# Sensors.net
KiCad netlist of a schematic drawn in Altium Designer
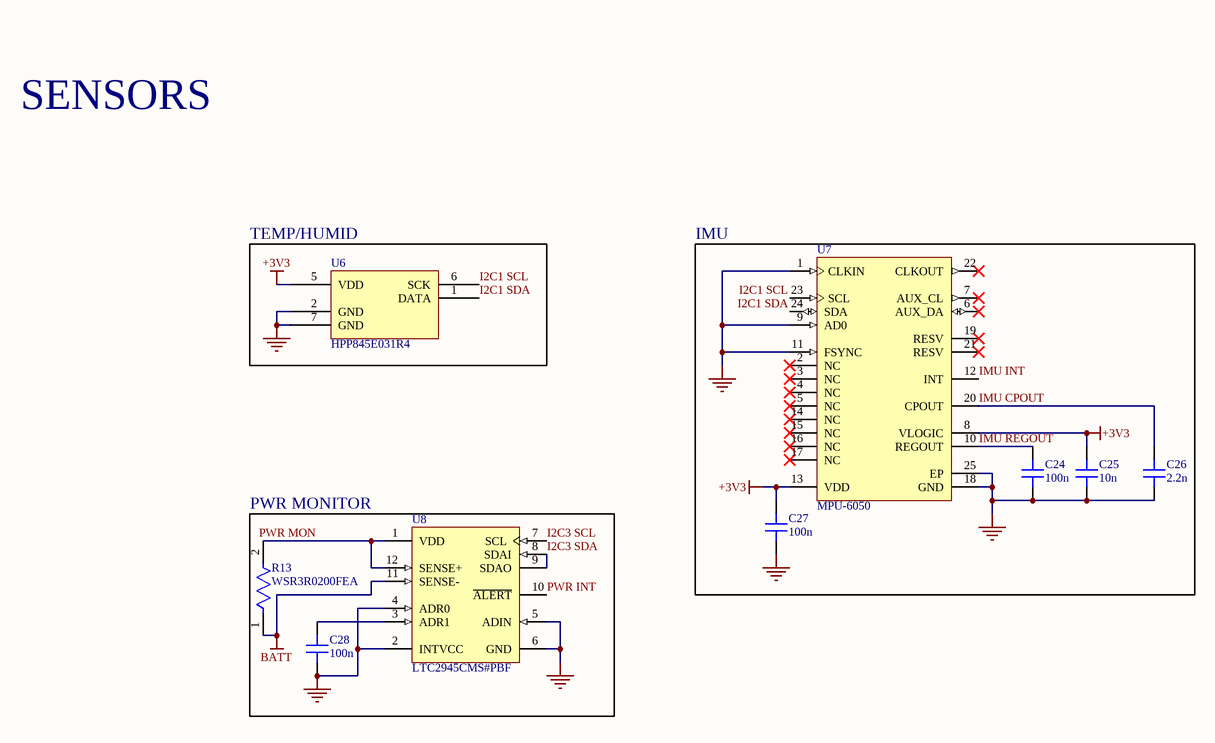
[diagram p0: Sensors.SchDoc]

(export (version "E")
  (design (tool "Eeschema 10.0.6"))
  (components
    (comp (ref "C24")
      (value "100n")
      (footprint "CAP 0402_1005")
      (description "CAP CER 100NF 10V X7R 0402")
      (fields (field (name "PART NUMBER") "CL05B104KP5VPNC"))
      (libsource (lib "Celestial Altium Library - altium_library") (part "Capacitor"))
    )
    (comp (ref "C25")
      (value "10n")
      (footprint "CAP 0402_1005")
      (description "CAP CER 0402 10NF 50V X7R 5%")
      (fields (field (name "PART NUMBER") "C0402C103J5RECAUTO"))
      (libsource (lib "Celestial Altium Library - altium_library") (part "Capacitor"))
    )
    (comp (ref "C26")
      (value "2.2n")
      (footprint "CAP 0402_1005")
      (description "CAP CER 0402 2.2NF 25V C0G 5%")
      (fields (field (name "PART NUMBER") "C0402C222J3GEC7867"))
      (libsource (lib "Celestial Altium Library - altium_library") (part "Capacitor"))
    )
    (comp (ref "C27")
      (value "100n")
      (footprint "CAP 0402_1005")
      (description "CAP CER 100NF 10V X7R 0402")
      (fields (field (name "PART NUMBER") "CL05B104KP5VPNC"))
      (libsource (lib "Celestial Altium Library - altium_library") (part "Capacitor"))
    )
    (comp (ref "C28")
      (value "100n")
      (footprint "CAP 0402_1005")
      (description "CAP CER 100NF 10V X7R 0402")
      (fields (field (name "PART NUMBER") "CL05B104KP5VPNC"))
      (libsource (lib "Celestial Altium Library - altium_library") (part "Capacitor"))
    )
    (comp (ref "R13")
      (value "WSR3R0200FEA")
      (footprint "FP-WSR3-MFG")
      (description "WSR3R0200FEA Res Metal Strip 4527 0.02 Ohm 1% 3W ±75ppm/°C Molded SMD SMD Embossed Plastic T/R")
      (fields (field (name "TOLERANCE") "1%"))
      (libsource (lib "Altium Content Vault") (part "1029c3af85768c4190bb7ad29bc67b5"))
    )
    (comp (ref "U6")
      (value "HPP845E031R4")
      (footprint "TE HPP845E031R4")
      (description "SENSOR HUMID/TEMP 3V I2C 2% SMD")
      (libsource (lib "Celestial Altium Library - altium_library") (part "TE HPP845E031R4"))
    )
    (comp (ref "U7")
      (value "MPU-6050")
      (footprint "IS-QFN-24_V")
      (fields (field (name "MANUFACTURER") "InvenSense"))
      (libsource (lib "Altium Content Vault") (part "IS-MPU-6050-QFN-24"))
    )
    (comp (ref "U8")
      (value "LTC2945CMS#PBF")
      (footprint "LT-MS-12_M")
      (description "Wide Range I2C Power Monitor, 12-pin SOP (MS-12), 0 to 70 degC, Pb-Free")
      (fields (field (name "MANUFACTURER") "Linear Technology"))
      (libsource (lib "Altium Content Vault") (part "LT-LTC2945-MS-12"))
    )
  )
  (nets
    (net (code "1") (name "+3V3") (class "Default")
      (node (ref "C25") (pin "2") (pinfunction "2_2") (pintype "passive"))
      (node (ref "C27") (pin "2") (pinfunction "2_2") (pintype "passive"))
      (node (ref "U6") (pin "5") (pinfunction "VDD_5") (pintype "passive"))
      (node (ref "U7") (pin "13") (pinfunction "VDD_13") (pintype "power_in"))
      (node (ref "U7") (pin "8") (pinfunction "VLOGIC_8") (pintype "power_in"))
    )
    (net (code "2") (name "/I2C1 SCL") (class "Default")
      (node (ref "U6") (pin "6") (pinfunction "SCK_6") (pintype "passive"))
      (node (ref "U7") (pin "23") (pinfunction "SCL_23") (pintype "input"))
    )
    (net (code "3") (name "/I2C1 SDA") (class "Default")
      (node (ref "U6") (pin "1") (pinfunction "DATA_1") (pintype "passive"))
      (node (ref "U7") (pin "24") (pinfunction "SDA_24") (pintype "bidirectional"))
    )
    (net (code "4") (name "/I2C3 SCL") (class "Default")
      (node (ref "U8") (pin "7") (pinfunction "SCL_7") (pintype "input"))
    )
    (net (code "5") (name "/I2C3 SDA") (class "Default")
      (node (ref "U8") (pin "8") (pinfunction "SDAI_8") (pintype "input"))
      (node (ref "U8") (pin "9") (pinfunction "SDAO_9") (pintype "open_collector"))
    )
    (net (code "6") (name "/IMU CPOUT") (class "Default")
      (node (ref "C26") (pin "2") (pinfunction "2_2") (pintype "passive"))
      (node (ref "U7") (pin "20") (pinfunction "CPOUT_20") (pintype "passive"))
    )
    (net (code "7") (name "/IMU INT") (class "Default")
      (node (ref "U7") (pin "12") (pinfunction "INT_12") (pintype "open_collector"))
    )
    (net (code "8") (name "/IMU REGOUT") (class "Default")
      (node (ref "C24") (pin "2") (pinfunction "2_2") (pintype "passive"))
      (node (ref "U7") (pin "10") (pinfunction "REGOUT_10") (pintype "passive"))
    )
    (net (code "9") (name "/PWR INT") (class "Default")
      (node (ref "U8") (pin "10") (pinfunction "~{ALERT}_10") (pintype "open_collector"))
    )
    (net (code "10") (name "/PWR MON") (class "Default")
      (node (ref "R13") (pin "2") (pinfunction "2_2") (pintype "passive"))
      (node (ref "U8") (pin "1") (pinfunction "VDD_1") (pintype "power_in"))
      (node (ref "U8") (pin "12") (pinfunction "SENSE+_12") (pintype "input"))
    )
    (net (code "11") (name "BATT") (class "Default")
      (node (ref "R13") (pin "1") (pinfunction "1_1") (pintype "passive"))
      (node (ref "U8") (pin "11") (pinfunction "SENSE-_11") (pintype "input"))
    )
    (net (code "12") (name "GND") (class "Default")
      (node (ref "C24") (pin "1") (pinfunction "1_1") (pintype "passive"))
      (node (ref "C25") (pin "1") (pinfunction "1_1") (pintype "passive"))
      (node (ref "C26") (pin "1") (pinfunction "1_1") (pintype "passive"))
      (node (ref "C27") (pin "1") (pinfunction "1_1") (pintype "passive"))
      (node (ref "C28") (pin "1") (pinfunction "1_1") (pintype "passive"))
      (node (ref "U6") (pin "2") (pinfunction "GND_2") (pintype "passive"))
      (node (ref "U6") (pin "7") (pinfunction "GND_7") (pintype "passive"))
      (node (ref "U7") (pin "1") (pinfunction "CLKIN_1") (pintype "input"))
      (node (ref "U7") (pin "11") (pinfunction "FSYNC_11") (pintype "input"))
      (node (ref "U7") (pin "18") (pinfunction "GND_18") (pintype "power_in"))
      (node (ref "U7") (pin "25") (pinfunction "EP_25") (pintype "power_in"))
      (node (ref "U7") (pin "9") (pinfunction "AD0_9") (pintype "input"))
      (node (ref "U8") (pin "2") (pinfunction "INTVCC_2") (pintype "power_in"))
      (node (ref "U8") (pin "4") (pinfunction "ADR0_4") (pintype "input"))
      (node (ref "U8") (pin "5") (pinfunction "ADIN_5") (pintype "input"))
      (node (ref "U8") (pin "6") (pinfunction "GND_6") (pintype "power_in"))
    )
    (net (code "13") (name "Net-(U8-ADR1)") (class "Default")
      (node (ref "C28") (pin "2") (pinfunction "2_2") (pintype "passive"))
      (node (ref "U8") (pin "3") (pinfunction "ADR1_3") (pintype "input"))
    )
    (net (code "14") (name "unconnected-(U7-AUX_CL-Pad7)") (class "Default")
      (node (ref "U7") (pin "7") (pinfunction "AUX_CL_7") (pintype "output+no_connect"))
    )
    (net (code "15") (name "unconnected-(U7-AUX_DA-Pad6)") (class "Default")
      (node (ref "U7") (pin "6") (pinfunction "AUX_DA_6") (pintype "bidirectional+no_connect"))
    )
    (net (code "16") (name "unconnected-(U7-CLKOUT-Pad22)") (class "Default")
      (node (ref "U7") (pin "22") (pinfunction "CLKOUT_22") (pintype "output+no_connect"))
    )
    (net (code "17") (name "unconnected-(U7-NC-Pad2)") (class "Default")
      (node (ref "U7") (pin "2") (pinfunction "NC_2") (pintype "passive+no_connect"))
    )
    (net (code "18") (name "unconnected-(U7-NC-Pad3)") (class "Default")
      (node (ref "U7") (pin "3") (pinfunction "NC_3") (pintype "passive+no_connect"))
    )
    (net (code "19") (name "unconnected-(U7-NC-Pad4)") (class "Default")
      (node (ref "U7") (pin "4") (pinfunction "NC_4") (pintype "passive+no_connect"))
    )
    (net (code "20") (name "unconnected-(U7-NC-Pad5)") (class "Default")
      (node (ref "U7") (pin "5") (pinfunction "NC_5") (pintype "passive+no_connect"))
    )
    (net (code "21") (name "unconnected-(U7-NC-Pad14)") (class "Default")
      (node (ref "U7") (pin "14") (pinfunction "NC_14") (pintype "passive+no_connect"))
    )
    (net (code "22") (name "unconnected-(U7-NC-Pad15)") (class "Default")
      (node (ref "U7") (pin "15") (pinfunction "NC_15") (pintype "passive+no_connect"))
    )
    (net (code "23") (name "unconnected-(U7-NC-Pad16)") (class "Default")
      (node (ref "U7") (pin "16") (pinfunction "NC_16") (pintype "passive+no_connect"))
    )
    (net (code "24") (name "unconnected-(U7-NC-Pad17)") (class "Default")
      (node (ref "U7") (pin "17") (pinfunction "NC_17") (pintype "passive+no_connect"))
    )
    (net (code "25") (name "unconnected-(U7-RESV-Pad19)") (class "Default")
      (node (ref "U7") (pin "19") (pinfunction "RESV_19") (pintype "passive+no_connect"))
    )
    (net (code "26") (name "unconnected-(U7-RESV-Pad21)") (class "Default")
      (node (ref "U7") (pin "21") (pinfunction "RESV_21") (pintype "passive+no_connect"))
    )
  )
)
